# divtiesus_v10_tiesus_del_to.net
KiCad netlist of a schematic drawn in EAGLE
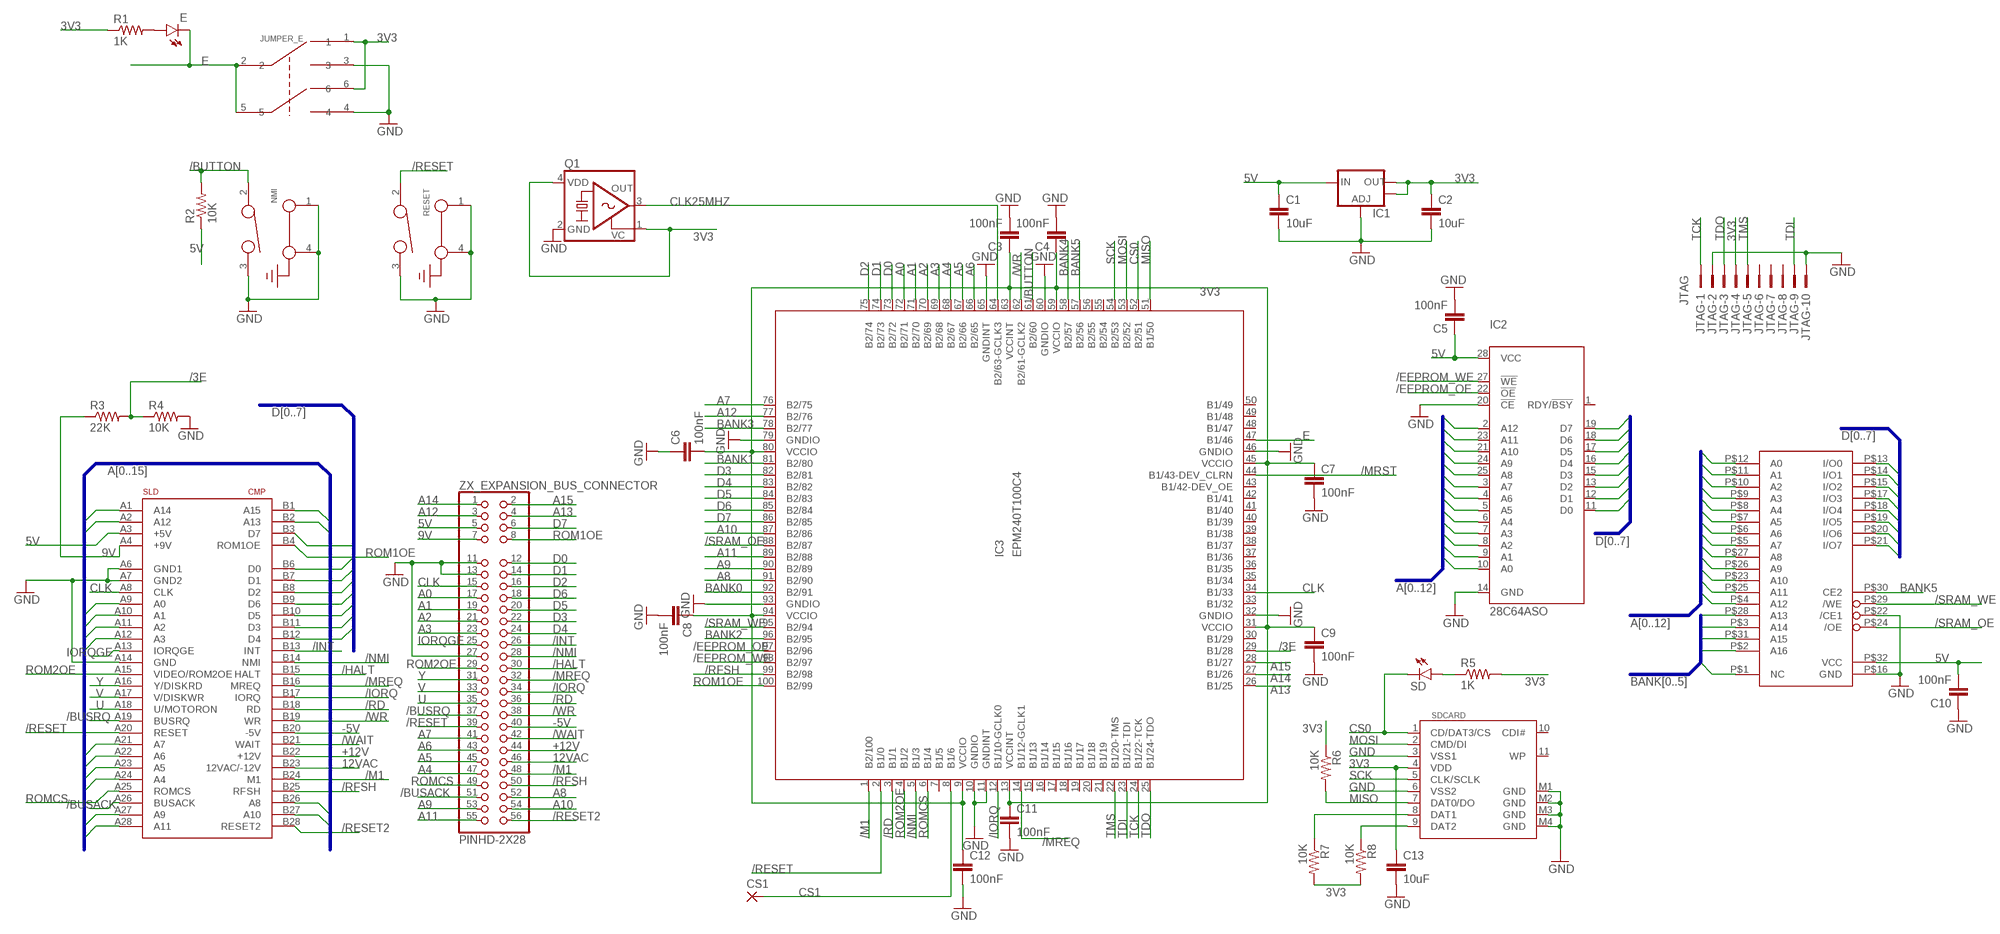
[diagram p0: schematic, sheet 1]

(export (version "E")
  (design (tool "Eeschema 10.0.6"))
  (components
    (comp (ref "C1")
      (value "10uF")
      (footprint "eagle-import:C0805")
      (libsource (lib "eagle-import") (part "C-EUC0805"))
    )
    (comp (ref "C2")
      (value "10uF")
      (footprint "eagle-import:C0805")
      (libsource (lib "eagle-import") (part "C-EUC0805"))
    )
    (comp (ref "C3")
      (value "100nF")
      (footprint "eagle-import:C0603K")
      (libsource (lib "eagle-import") (part "C-EUC0603K"))
    )
    (comp (ref "C4")
      (value "100nF")
      (footprint "eagle-import:C0603K")
      (libsource (lib "eagle-import") (part "C-EUC0603K"))
    )
    (comp (ref "C5")
      (value "100nF")
      (footprint "eagle-import:C0603K")
      (libsource (lib "eagle-import") (part "C-EUC0603K"))
    )
    (comp (ref "C6")
      (value "100nF")
      (footprint "eagle-import:C0603K")
      (libsource (lib "eagle-import") (part "C-EUC0603K"))
    )
    (comp (ref "C7")
      (value "100nF")
      (footprint "eagle-import:C0603K")
      (libsource (lib "eagle-import") (part "C-EUC0603K"))
    )
    (comp (ref "C8")
      (value "100nF")
      (footprint "eagle-import:C0603K")
      (libsource (lib "eagle-import") (part "C-EUC0603K"))
    )
    (comp (ref "C9")
      (value "100nF")
      (footprint "eagle-import:C0603K")
      (libsource (lib "eagle-import") (part "C-EUC0603K"))
    )
    (comp (ref "C10")
      (value "100nF")
      (footprint "eagle-import:C0603K")
      (libsource (lib "eagle-import") (part "C-EUC0603K"))
    )
    (comp (ref "C11")
      (value "100nF")
      (footprint "eagle-import:C0603K")
      (libsource (lib "eagle-import") (part "C-EUC0603K"))
    )
    (comp (ref "C12")
      (value "100nF")
      (footprint "eagle-import:C0603K")
      (libsource (lib "eagle-import") (part "C-EUC0603K"))
    )
    (comp (ref "C13")
      (value "10uF")
      (footprint "eagle-import:C0805")
      (libsource (lib "eagle-import") (part "C-EUC0805"))
    )
    (comp (ref "CS1")
      (value "SMD2")
      (footprint "eagle-import:SMD1,27-2,54")
      (libsource (lib "eagle-import") (part "SMD2"))
    )
    (comp (ref "E")
      (value "LEDCHIPLED_0805")
      (footprint "eagle-import:CHIPLED_0805")
      (libsource (lib "eagle-import") (part "LEDCHIPLED_0805"))
    )
    (comp (ref "IC1")
      (value "V_REG_LM1117SOT223")
      (footprint "eagle-import:SOT223")
      (libsource (lib "eagle-import") (part "V_REG_LM1117SOT223"))
    )
    (comp (ref "IC2")
      (value "28C64ASO")
      (footprint "eagle-import:SO28W")
      (fields (field (name "MPN") "CAT28C64BWI-12"))
      (libsource (lib "eagle-import") (part "2864ASOC"))
    )
    (comp (ref "IC3")
      (value "EPM240T100C4")
      (footprint "eagle-import:TQFP100")
      (libsource (lib "eagle-import") (part "EPM240T100C4"))
    )
    (comp (ref "IC4")
      (value "IS65C1024ALSO32")
      (footprint "eagle-import:SO32-545MIL")
      (libsource (lib "eagle-import") (part "IS65C1024ALSO32"))
    )
    (comp (ref "JTAG")
      (value "JTAG")
      (footprint "eagle-import:PAK100_2500-10")
      (fields (field (name "MF") "3M") (field (name "MPN") "2510-6002UB"))
      (libsource (lib "eagle-import") (part "2510-"))
    )
    (comp (ref "JUMPER_E")
      (value "SWITCH_SMD_6PIN")
      (footprint "eagle-import:SMD-6PIN")
      (libsource (lib "eagle-import") (part "SWITCH_SMD_6PIN"))
    )
    (comp (ref "NMI")
      (value "431256083716")
      (footprint "eagle-import:431256083716")
      (libsource (lib "eagle-import") (part "431256083716"))
    )
    (comp (ref "Q1")
      (value "KXO-VCTCXO-SINE-84")
      (footprint "eagle-import:3.2X2.5_KXO-84-VCTCXO")
      (libsource (lib "eagle-import") (part "KXO-VCTCXO-SINE-84"))
    )
    (comp (ref "R1")
      (value "1K")
      (footprint "eagle-import:R0603")
      (libsource (lib "eagle-import") (part "R-US_R0603"))
    )
    (comp (ref "R2")
      (value "10K")
      (footprint "eagle-import:R0603")
      (libsource (lib "eagle-import") (part "R-US_R0603"))
    )
    (comp (ref "R3")
      (value "22K")
      (footprint "eagle-import:R0603")
      (libsource (lib "eagle-import") (part "R-US_R0603"))
    )
    (comp (ref "R4")
      (value "10K")
      (footprint "eagle-import:R0603")
      (libsource (lib "eagle-import") (part "R-US_R0603"))
    )
    (comp (ref "R5")
      (value "1K")
      (footprint "eagle-import:R0603")
      (libsource (lib "eagle-import") (part "R-US_R0603"))
    )
    (comp (ref "R6")
      (value "10K")
      (footprint "eagle-import:R0603")
      (libsource (lib "eagle-import") (part "R-US_R0603"))
    )
    (comp (ref "R7")
      (value "10K")
      (footprint "eagle-import:R0603")
      (libsource (lib "eagle-import") (part "R-US_R0603"))
    )
    (comp (ref "R8")
      (value "10K")
      (footprint "eagle-import:R0603")
      (libsource (lib "eagle-import") (part "R-US_R0603"))
    )
    (comp (ref "RESET")
      (value "431256083716")
      (footprint "eagle-import:431256083716")
      (libsource (lib "eagle-import") (part "431256083716"))
    )
    (comp (ref "SD")
      (value "LEDCHIPLED_0805")
      (footprint "eagle-import:CHIPLED_0805")
      (libsource (lib "eagle-import") (part "LEDCHIPLED_0805"))
    )
    (comp (ref "SDCARD")
      (value "SDCARD")
      (footprint "eagle-import:SDCMF-10915W010")
      (libsource (lib "eagle-import") (part "SDCARD"))
    )
    (comp (ref "U$1")
      (value "CONECTOR_BUS_TRASERO")
      (footprint "eagle-import:CONECTOR_SIMPLE_CARA")
      (libsource (lib "eagle-import") (part "CONECTOR_BUS_TRASERO"))
    )
    (comp (ref "ZX_EXPANSION_BUS_CONNECTOR")
      (value "PINHD-2X28")
      (footprint "eagle-import:2X28")
      (libsource (lib "eagle-import") (part "PINHD-2X28"))
    )
  )
  (nets
    (net (code "1") (name "/+12V") (class "Default")
      (node (ref "U$1") (pin "B22") (pinfunction "+12V_B22") (pintype "bidirectional"))
      (node (ref "ZX_EXPANSION_BUS_CONNECTOR") (pin "44") (pinfunction "44_44") (pintype "passive"))
    )
    (net (code "2") (name "/-5V") (class "Default")
      (node (ref "U$1") (pin "B20") (pinfunction "-5V_B20") (pintype "bidirectional"))
      (node (ref "ZX_EXPANSION_BUS_CONNECTOR") (pin "40") (pinfunction "40_40") (pintype "passive"))
    )
    (net (code "3") (name "/3V3") (class "Default")
      (node (ref "C11") (pin "1") (pinfunction "1_1") (pintype "passive"))
      (node (ref "C12") (pin "1") (pinfunction "1_1") (pintype "passive"))
      (node (ref "C13") (pin "1") (pinfunction "1_1") (pintype "passive"))
      (node (ref "C2") (pin "1") (pinfunction "1_1") (pintype "passive"))
      (node (ref "C3") (pin "1") (pinfunction "1_1") (pintype "passive"))
      (node (ref "C4") (pin "1") (pinfunction "1_1") (pintype "passive"))
      (node (ref "C6") (pin "2") (pinfunction "2_2") (pintype "passive"))
      (node (ref "C7") (pin "1") (pinfunction "1_1") (pintype "passive"))
      (node (ref "C8") (pin "1") (pinfunction "1_1") (pintype "passive"))
      (node (ref "C9") (pin "1") (pinfunction "1_1") (pintype "passive"))
      (node (ref "IC1") (pin "2") (pinfunction "OUT_2") (pintype "output"))
      (node (ref "IC1") (pin "4") (pinfunction "OUT_4") (pintype "output"))
      (node (ref "IC3") (pin "13") (pinfunction "VCCINT_13") (pintype "power_in"))
      (node (ref "IC3") (pin "31") (pinfunction "VCCIO_31") (pintype "power_in"))
      (node (ref "IC3") (pin "45") (pinfunction "VCCIO_45") (pintype "power_in"))
      (node (ref "IC3") (pin "59") (pinfunction "VCCIO_59") (pintype "power_in"))
      (node (ref "IC3") (pin "63") (pinfunction "VCCINT_63") (pintype "power_in"))
      (node (ref "IC3") (pin "80") (pinfunction "VCCIO_80") (pintype "power_in"))
      (node (ref "IC3") (pin "9") (pinfunction "VCCIO_9") (pintype "power_in"))
      (node (ref "IC3") (pin "94") (pinfunction "VCCIO_94") (pintype "power_in"))
      (node (ref "JTAG") (pin "4") (pinfunction "KL_4") (pintype "passive"))
      (node (ref "JUMPER_E") (pin "1") (pinfunction "1_1") (pintype "bidirectional"))
      (node (ref "JUMPER_E") (pin "6") (pinfunction "6_6") (pintype "bidirectional"))
      (node (ref "Q1") (pin "1") (pinfunction "VC_1") (pintype "input"))
      (node (ref "Q1") (pin "4") (pinfunction "VDD_4") (pintype "power_in"))
      (node (ref "R1") (pin "1") (pinfunction "1_1") (pintype "passive"))
      (node (ref "R5") (pin "2") (pinfunction "2_2") (pintype "passive"))
      (node (ref "R6") (pin "1") (pinfunction "1_1") (pintype "passive"))
      (node (ref "R7") (pin "2") (pinfunction "2_2") (pintype "passive"))
      (node (ref "R8") (pin "2") (pinfunction "2_2") (pintype "passive"))
      (node (ref "SDCARD") (pin "4") (pinfunction "VDD_4") (pintype "power_in"))
    )
    (net (code "4") (name "/5V") (class "Default")
      (node (ref "C1") (pin "1") (pinfunction "1_1") (pintype "passive"))
      (node (ref "C10") (pin "2") (pinfunction "2_2") (pintype "passive"))
      (node (ref "C5") (pin "1") (pinfunction "1_1") (pintype "passive"))
      (node (ref "IC1") (pin "3") (pinfunction "IN_3") (pintype "input"))
      (node (ref "IC2") (pin "28") (pinfunction "VCC_28") (pintype "power_in"))
      (node (ref "IC4") (pin "P$32") (pinfunction "VCC_P$32") (pintype "input"))
      (node (ref "R2") (pin "1") (pinfunction "1_1") (pintype "passive"))
      (node (ref "U$1") (pin "A3") (pinfunction "+5V_A3") (pintype "bidirectional"))
      (node (ref "ZX_EXPANSION_BUS_CONNECTOR") (pin "5") (pinfunction "5_5") (pintype "passive"))
    )
    (net (code "5") (name "/9V") (class "Default")
      (node (ref "R3") (pin "1") (pinfunction "1_1") (pintype "passive"))
      (node (ref "U$1") (pin "A4") (pinfunction "+9V_A4") (pintype "bidirectional"))
      (node (ref "ZX_EXPANSION_BUS_CONNECTOR") (pin "7") (pinfunction "7_7") (pintype "passive"))
    )
    (net (code "6") (name "/12VAC") (class "Default")
      (node (ref "U$1") (pin "B23") (pinfunction "12VAC/-12V_B23") (pintype "bidirectional"))
      (node (ref "ZX_EXPANSION_BUS_CONNECTOR") (pin "46") (pinfunction "46_46") (pintype "passive"))
    )
    (net (code "7") (name "/A0") (class "Default")
      (node (ref "IC2") (pin "10") (pinfunction "A0_10") (pintype "input"))
      (node (ref "IC3") (pin "72") (pinfunction "B2/71_72") (pintype "bidirectional"))
      (node (ref "IC4") (pin "P$12") (pinfunction "A0_P$12") (pintype "input"))
      (node (ref "U$1") (pin "A9") (pinfunction "A0_A9") (pintype "bidirectional"))
      (node (ref "ZX_EXPANSION_BUS_CONNECTOR") (pin "17") (pinfunction "17_17") (pintype "passive"))
    )
    (net (code "8") (name "/A1") (class "Default")
      (node (ref "IC2") (pin "9") (pinfunction "A1_9") (pintype "input"))
      (node (ref "IC3") (pin "71") (pinfunction "B2/70_71") (pintype "bidirectional"))
      (node (ref "IC4") (pin "P$11") (pinfunction "A1_P$11") (pintype "input"))
      (node (ref "U$1") (pin "A10") (pinfunction "A1_A10") (pintype "bidirectional"))
      (node (ref "ZX_EXPANSION_BUS_CONNECTOR") (pin "19") (pinfunction "19_19") (pintype "passive"))
    )
    (net (code "9") (name "/A2") (class "Default")
      (node (ref "IC2") (pin "8") (pinfunction "A2_8") (pintype "input"))
      (node (ref "IC3") (pin "70") (pinfunction "B2/69_70") (pintype "bidirectional"))
      (node (ref "IC4") (pin "P$10") (pinfunction "A2_P$10") (pintype "input"))
      (node (ref "U$1") (pin "A11") (pinfunction "A2_A11") (pintype "bidirectional"))
      (node (ref "ZX_EXPANSION_BUS_CONNECTOR") (pin "21") (pinfunction "21_21") (pintype "passive"))
    )
    (net (code "10") (name "/A3") (class "Default")
      (node (ref "IC2") (pin "7") (pinfunction "A3_7") (pintype "input"))
      (node (ref "IC3") (pin "69") (pinfunction "B2/68_69") (pintype "bidirectional"))
      (node (ref "IC4") (pin "P$9") (pinfunction "A3_P$9") (pintype "input"))
      (node (ref "U$1") (pin "A12") (pinfunction "A3_A12") (pintype "bidirectional"))
      (node (ref "ZX_EXPANSION_BUS_CONNECTOR") (pin "23") (pinfunction "23_23") (pintype "passive"))
    )
    (net (code "11") (name "/A4") (class "Default")
      (node (ref "IC2") (pin "6") (pinfunction "A4_6") (pintype "input"))
      (node (ref "IC3") (pin "68") (pinfunction "B2/67_68") (pintype "bidirectional"))
      (node (ref "IC4") (pin "P$8") (pinfunction "A4_P$8") (pintype "input"))
      (node (ref "U$1") (pin "A24") (pinfunction "A4_A24") (pintype "bidirectional"))
      (node (ref "ZX_EXPANSION_BUS_CONNECTOR") (pin "47") (pinfunction "47_47") (pintype "passive"))
    )
    (net (code "12") (name "/A5") (class "Default")
      (node (ref "IC2") (pin "5") (pinfunction "A5_5") (pintype "input"))
      (node (ref "IC3") (pin "67") (pinfunction "B2/66_67") (pintype "bidirectional"))
      (node (ref "IC4") (pin "P$7") (pinfunction "A5_P$7") (pintype "input"))
      (node (ref "U$1") (pin "A23") (pinfunction "A5_A23") (pintype "bidirectional"))
      (node (ref "ZX_EXPANSION_BUS_CONNECTOR") (pin "45") (pinfunction "45_45") (pintype "passive"))
    )
    (net (code "13") (name "/A6") (class "Default")
      (node (ref "IC2") (pin "4") (pinfunction "A6_4") (pintype "input"))
      (node (ref "IC3") (pin "66") (pinfunction "B2/65_66") (pintype "bidirectional"))
      (node (ref "IC4") (pin "P$6") (pinfunction "A6_P$6") (pintype "input"))
      (node (ref "U$1") (pin "A22") (pinfunction "A6_A22") (pintype "bidirectional"))
      (node (ref "ZX_EXPANSION_BUS_CONNECTOR") (pin "43") (pinfunction "43_43") (pintype "passive"))
    )
    (net (code "14") (name "/A7") (class "Default")
      (node (ref "IC2") (pin "3") (pinfunction "A7_3") (pintype "input"))
      (node (ref "IC3") (pin "76") (pinfunction "B2/75_76") (pintype "bidirectional"))
      (node (ref "IC4") (pin "P$5") (pinfunction "A7_P$5") (pintype "input"))
      (node (ref "U$1") (pin "A21") (pinfunction "A7_A21") (pintype "bidirectional"))
      (node (ref "ZX_EXPANSION_BUS_CONNECTOR") (pin "41") (pinfunction "41_41") (pintype "passive"))
    )
    (net (code "15") (name "/A8") (class "Default")
      (node (ref "IC2") (pin "25") (pinfunction "A8_25") (pintype "input"))
      (node (ref "IC3") (pin "91") (pinfunction "B2/90_91") (pintype "bidirectional"))
      (node (ref "IC4") (pin "P$27") (pinfunction "A8_P$27") (pintype "input"))
      (node (ref "U$1") (pin "B26") (pinfunction "A8_B26") (pintype "bidirectional"))
      (node (ref "ZX_EXPANSION_BUS_CONNECTOR") (pin "52") (pinfunction "52_52") (pintype "passive"))
    )
    (net (code "16") (name "/A9") (class "Default")
      (node (ref "IC2") (pin "24") (pinfunction "A9_24") (pintype "input"))
      (node (ref "IC3") (pin "90") (pinfunction "B2/89_90") (pintype "bidirectional"))
      (node (ref "IC4") (pin "P$26") (pinfunction "A9_P$26") (pintype "input"))
      (node (ref "U$1") (pin "A27") (pinfunction "A9_A27") (pintype "bidirectional"))
      (node (ref "ZX_EXPANSION_BUS_CONNECTOR") (pin "53") (pinfunction "53_53") (pintype "passive"))
    )
    (net (code "17") (name "/A10") (class "Default")
      (node (ref "IC2") (pin "21") (pinfunction "A10_21") (pintype "input"))
      (node (ref "IC3") (pin "87") (pinfunction "B2/86_87") (pintype "bidirectional"))
      (node (ref "IC4") (pin "P$23") (pinfunction "A10_P$23") (pintype "input"))
      (node (ref "U$1") (pin "B27") (pinfunction "A10_B27") (pintype "bidirectional"))
      (node (ref "ZX_EXPANSION_BUS_CONNECTOR") (pin "54") (pinfunction "54_54") (pintype "passive"))
    )
    (net (code "18") (name "/A11") (class "Default")
      (node (ref "IC2") (pin "23") (pinfunction "A11_23") (pintype "input"))
      (node (ref "IC3") (pin "89") (pinfunction "B2/88_89") (pintype "bidirectional"))
      (node (ref "IC4") (pin "P$25") (pinfunction "A11_P$25") (pintype "input"))
      (node (ref "U$1") (pin "A28") (pinfunction "A11_A28") (pintype "bidirectional"))
      (node (ref "ZX_EXPANSION_BUS_CONNECTOR") (pin "55") (pinfunction "55_55") (pintype "passive"))
    )
    (net (code "19") (name "/A12") (class "Default")
      (node (ref "IC2") (pin "2") (pinfunction "A12_2") (pintype "input"))
      (node (ref "IC3") (pin "77") (pinfunction "B2/76_77") (pintype "bidirectional"))
      (node (ref "IC4") (pin "P$4") (pinfunction "A12_P$4") (pintype "input"))
      (node (ref "U$1") (pin "A2") (pinfunction "A12_A2") (pintype "bidirectional"))
      (node (ref "ZX_EXPANSION_BUS_CONNECTOR") (pin "3") (pinfunction "3_3") (pintype "passive"))
    )
    (net (code "20") (name "/A13") (class "Default")
      (node (ref "IC3") (pin "26") (pinfunction "B1/25_26") (pintype "bidirectional"))
      (node (ref "U$1") (pin "B2") (pinfunction "A13_B2") (pintype "bidirectional"))
      (node (ref "ZX_EXPANSION_BUS_CONNECTOR") (pin "4") (pinfunction "4_4") (pintype "passive"))
    )
    (net (code "21") (name "/A14") (class "Default")
      (node (ref "IC3") (pin "27") (pinfunction "B1/26_27") (pintype "bidirectional"))
      (node (ref "U$1") (pin "A1") (pinfunction "A14_A1") (pintype "bidirectional"))
      (node (ref "ZX_EXPANSION_BUS_CONNECTOR") (pin "1") (pinfunction "1_1") (pintype "passive"))
    )
    (net (code "22") (name "/A15") (class "Default")
      (node (ref "IC3") (pin "28") (pinfunction "B1/27_28") (pintype "bidirectional"))
      (node (ref "U$1") (pin "B1") (pinfunction "A15_B1") (pintype "bidirectional"))
      (node (ref "ZX_EXPANSION_BUS_CONNECTOR") (pin "2") (pinfunction "2_2") (pintype "passive"))
    )
    (net (code "25") (name "/BANK0") (class "Default")
      (node (ref "IC3") (pin "92") (pinfunction "B2/91_92") (pintype "bidirectional"))
      (node (ref "IC4") (pin "P$28") (pinfunction "A13_P$28") (pintype "input"))
    )
    (net (code "26") (name "/BANK1") (class "Default")
      (node (ref "IC3") (pin "81") (pinfunction "B2/80_81") (pintype "bidirectional"))
      (node (ref "IC4") (pin "P$3") (pinfunction "A14_P$3") (pintype "input"))
    )
    (net (code "27") (name "/BANK2") (class "Default")
      (node (ref "IC3") (pin "96") (pinfunction "B2/95_96") (pintype "bidirectional"))
      (node (ref "IC4") (pin "P$31") (pinfunction "A15_P$31") (pintype "input"))
    )
    (net (code "28") (name "/BANK3") (class "Default")
      (node (ref "IC3") (pin "78") (pinfunction "B2/77_78") (pintype "bidirectional"))
      (node (ref "IC4") (pin "P$2") (pinfunction "A16_P$2") (pintype "input"))
    )
    (net (code "29") (name "/BANK4") (class "Default")
      (node (ref "IC3") (pin "58") (pinfunction "B2/57_58") (pintype "bidirectional"))
      (node (ref "IC4") (pin "P$1") (pinfunction "NC_P$1") (pintype "input"))
    )
    (net (code "30") (name "/BANK5") (class "Default")
      (node (ref "IC3") (pin "57") (pinfunction "B2/56_57") (pintype "bidirectional"))
      (node (ref "IC4") (pin "P$30") (pinfunction "CE2_P$30") (pintype "input"))
    )
    (net (code "32") (name "/CLK") (class "Default")
      (node (ref "IC3") (pin "34") (pinfunction "B1/33_34") (pintype "bidirectional"))
      (node (ref "U$1") (pin "A8") (pinfunction "CLK_A8") (pintype "bidirectional"))
      (node (ref "ZX_EXPANSION_BUS_CONNECTOR") (pin "15") (pinfunction "15_15") (pintype "passive"))
    )
    (net (code "33") (name "/CLK25MHZ") (class "Default")
      (node (ref "IC3") (pin "64") (pinfunction "B2/63-GCLK3_64") (pintype "bidirectional"))
      (node (ref "Q1") (pin "3") (pinfunction "OUT_3") (pintype "output"))
    )
    (net (code "34") (name "/CS0") (class "Default")
      (node (ref "IC3") (pin "52") (pinfunction "B2/51_52") (pintype "bidirectional"))
      (node (ref "SD") (pin "C") (pinfunction "C_C") (pintype "passive"))
      (node (ref "SDCARD") (pin "1") (pinfunction "CD/DAT3/CS_1") (pintype "bidirectional"))
    )
    (net (code "35") (name "/CS1") (class "Default")
      (node (ref "CS1") (pin "1") (pinfunction "P_1") (pintype "passive"))
      (node (ref "IC3") (pin "8") (pinfunction "B1/6_8") (pintype "bidirectional"))
    )
    (net (code "36") (name "/D0") (class "Default")
      (node (ref "IC2") (pin "11") (pinfunction "D0_11") (pintype "tri_state"))
      (node (ref "IC3") (pin "73") (pinfunction "B2/72_73") (pintype "bidirectional"))
      (node (ref "IC4") (pin "P$13") (pinfunction "I/O0_P$13") (pintype "bidirectional"))
      (node (ref "U$1") (pin "B6") (pinfunction "D0_B6") (pintype "bidirectional"))
      (node (ref "ZX_EXPANSION_BUS_CONNECTOR") (pin "12") (pinfunction "12_12") (pintype "passive"))
    )
    (net (code "37") (name "/D1") (class "Default")
      (node (ref "IC2") (pin "12") (pinfunction "D1_12") (pintype "tri_state"))
      (node (ref "IC3") (pin "74") (pinfunction "B2/73_74") (pintype "bidirectional"))
      (node (ref "IC4") (pin "P$14") (pinfunction "I/O1_P$14") (pintype "bidirectional"))
      (node (ref "U$1") (pin "B7") (pinfunction "D1_B7") (pintype "bidirectional"))
      (node (ref "ZX_EXPANSION_BUS_CONNECTOR") (pin "14") (pinfunction "14_14") (pintype "passive"))
    )
    (net (code "38") (name "/D2") (class "Default")
      (node (ref "IC2") (pin "13") (pinfunction "D2_13") (pintype "tri_state"))
      (node (ref "IC3") (pin "75") (pinfunction "B2/74_75") (pintype "bidirectional"))
      (node (ref "IC4") (pin "P$15") (pinfunction "I/O2_P$15") (pintype "bidirectional"))
      (node (ref "U$1") (pin "B8") (pinfunction "D2_B8") (pintype "bidirectional"))
      (node (ref "ZX_EXPANSION_BUS_CONNECTOR") (pin "16") (pinfunction "16_16") (pintype "passive"))
    )
    (net (code "39") (name "/D3") (class "Default")
      (node (ref "IC2") (pin "15") (pinfunction "D3_15") (pintype "tri_state"))
      (node (ref "IC3") (pin "82") (pinfunction "B2/81_82") (pintype "bidirectional"))
      (node (ref "IC4") (pin "P$17") (pinfunction "I/O3_P$17") (pintype "bidirectional"))
      (node (ref "U$1") (pin "B11") (pinfunction "D3_B11") (pintype "bidirectional"))
      (node (ref "ZX_EXPANSION_BUS_CONNECTOR") (pin "22") (pinfunction "22_22") (pintype "passive"))
    )
    (net (code "40") (name "/D4") (class "Default")
      (node (ref "IC2") (pin "16") (pinfunction "D4_16") (pintype "tri_state"))
      (node (ref "IC3") (pin "83") (pinfunction "B2/82_83") (pintype "bidirectional"))
      (node (ref "IC4") (pin "P$18") (pinfunction "I/O4_P$18") (pintype "bidirectional"))
      (node (ref "U$1") (pin "B12") (pinfunction "D4_B12") (pintype "bidirectional"))
      (node (ref "ZX_EXPANSION_BUS_CONNECTOR") (pin "24") (pinfunction "24_24") (pintype "passive"))
    )
    (net (code "41") (name "/D5") (class "Default")
      (node (ref "IC2") (pin "17") (pinfunction "D5_17") (pintype "tri_state"))
      (node (ref "IC3") (pin "84") (pinfunction "B2/83_84") (pintype "bidirectional"))
      (node (ref "IC4") (pin "P$19") (pinfunction "I/O5_P$19") (pintype "bidirectional"))
      (node (ref "U$1") (pin "B10") (pinfunction "D5_B10") (pintype "bidirectional"))
      (node (ref "ZX_EXPANSION_BUS_CONNECTOR") (pin "20") (pinfunction "20_20") (pintype "passive"))
    )
    (net (code "42") (name "/D6") (class "Default")
      (node (ref "IC2") (pin "18") (pinfunction "D6_18") (pintype "tri_state"))
      (node (ref "IC3") (pin "85") (pinfunction "B2/84_85") (pintype "bidirectional"))
      (node (ref "IC4") (pin "P$20") (pinfunction "I/O6_P$20") (pintype "bidirectional"))
      (node (ref "U$1") (pin "B9") (pinfunction "D6_B9") (pintype "bidirectional"))
      (node (ref "ZX_EXPANSION_BUS_CONNECTOR") (pin "18") (pinfunction "18_18") (pintype "passive"))
    )
    (net (code "43") (name "/D7") (class "Default")
      (node (ref "IC2") (pin "19") (pinfunction "D7_19") (pintype "tri_state"))
      (node (ref "IC3") (pin "86") (pinfunction "B2/85_86") (pintype "bidirectional"))
      (node (ref "IC4") (pin "P$21") (pinfunction "I/O7_P$21") (pintype "bidirectional"))
      (node (ref "U$1") (pin "B3") (pinfunction "D7_B3") (pintype "bidirectional"))
      (node (ref "ZX_EXPANSION_BUS_CONNECTOR") (pin "6") (pinfunction "6_6") (pintype "passive"))
    )
    (net (code "45") (name "/E") (class "Default")
      (node (ref "E") (pin "C") (pinfunction "C_C") (pintype "passive"))
      (node (ref "IC3") (pin "47") (pinfunction "B1/46_47") (pintype "bidirectional"))
      (node (ref "JUMPER_E") (pin "2") (pinfunction "2_2") (pintype "bidirectional"))
      (node (ref "JUMPER_E") (pin "5") (pinfunction "5_5") (pintype "bidirectional"))
    )
    (net (code "46") (name "/IORQGE") (class "Default")
      (node (ref "U$1") (pin "A13") (pinfunction "IORQGE_A13") (pintype "bidirectional"))
      (node (ref "ZX_EXPANSION_BUS_CONNECTOR") (pin "25") (pinfunction "25_25") (pintype "passive"))
    )
    (net (code "47") (name "/MISO") (class "Default")
      (node (ref "IC3") (pin "51") (pinfunction "B1/50_51") (pintype "bidirectional"))
      (node (ref "R6") (pin "2") (pinfunction "2_2") (pintype "passive"))
      (node (ref "SDCARD") (pin "7") (pinfunction "DAT0/DO_7") (pintype "bidirectional"))
    )
    (net (code "48") (name "/MOSI") (class "Default")
      (node (ref "IC3") (pin "53") (pinfunction "B2/52_53") (pintype "bidirectional"))
      (node (ref "SDCARD") (pin "2") (pinfunction "CMD/DI_2") (pintype "bidirectional"))
    )
    (net (code "49") (name "/ROM1OE") (class "Default")
      (node (ref "IC3") (pin "100") (pinfunction "B2/99_100") (pintype "bidirectional"))
      (node (ref "U$1") (pin "B4") (pinfunction "ROM1OE_B4") (pintype "bidirectional"))
      (node (ref "ZX_EXPANSION_BUS_CONNECTOR") (pin "8") (pinfunction "8_8") (pintype "passive"))
    )
    (net (code "50") (name "/ROM2OE") (class "Default")
      (node (ref "IC3") (pin "4") (pinfunction "B1/2_4") (pintype "bidirectional"))
      (node (ref "U$1") (pin "A15") (pinfunction "VIDEO/ROM2OE_A15") (pintype "bidirectional"))
      (node (ref "ZX_EXPANSION_BUS_CONNECTOR") (pin "29") (pinfunction "29_29") (pintype "passive"))
    )
    (net (code "51") (name "/ROMCS") (class "Default")
      (node (ref "IC3") (pin "6") (pinfunction "B1/4_6") (pintype "bidirectional"))
      (node (ref "U$1") (pin "A25") (pinfunction "ROMCS_A25") (pintype "bidirectional"))
      (node (ref "ZX_EXPANSION_BUS_CONNECTOR") (pin "49") (pinfunction "49_49") (pintype "passive"))
    )
    (net (code "52") (name "/SCK") (class "Default")
      (node (ref "IC3") (pin "54") (pinfunction "B2/53_54") (pintype "bidirectional"))
      (node (ref "SDCARD") (pin "5") (pinfunction "CLK/SCLK_5") (pintype "bidirectional"))
    )
    (net (code "53") (name "/TCK") (class "Default")
      (node (ref "IC3") (pin "24") (pinfunction "B1/22-TCK_24") (pintype "input"))
      (node (ref "JTAG") (pin "1") (pinfunction "KL_1") (pintype "passive"))
    )
    (net (code "54") (name "/TDI") (class "Default")
      (node (ref "IC3") (pin "23") (pinfunction "B1/21-TDI_23") (pintype "input"))
      (node (ref "JTAG") (pin "9") (pinfunction "KL_9") (pintype "passive"))
    )
    (net (code "55") (name "/TDO") (class "Default")
      (node (ref "IC3") (pin "25") (pinfunction "B1/24-TDO_25") (pintype "output"))
      (node (ref "JTAG") (pin "3") (pinfunction "KL_3") (pintype "passive"))
    )
    (net (code "56") (name "/TMS") (class "Default")
      (node (ref "IC3") (pin "22") (pinfunction "B1/20-TMS_22") (pintype "input"))
      (node (ref "JTAG") (pin "5") (pinfunction "KL_5") (pintype "passive"))
    )
    (net (code "57") (name "/U") (class "Default")
      (node (ref "U$1") (pin "A18") (pinfunction "U/MOTORON_A18") (pintype "bidirectional"))
      (node (ref "ZX_EXPANSION_BUS_CONNECTOR") (pin "35") (pinfunction "35_35") (pintype "passive"))
    )
    (net (code "58") (name "/V") (class "Default")
      (node (ref "U$1") (pin "A17") (pinfunction "V/DISKWR_A17") (pintype "bidirectional"))
      (node (ref "ZX_EXPANSION_BUS_CONNECTOR") (pin "33") (pinfunction "33_33") (pintype "passive"))
    )
    (net (code "59") (name "/Y") (class "Default")
      (node (ref "U$1") (pin "A16") (pinfunction "Y/DISKRD_A16") (pintype "bidirectional"))
      (node (ref "ZX_EXPANSION_BUS_CONNECTOR") (pin "31") (pinfunction "31_31") (pintype "passive"))
    )
    (net (code "60") (name "/{slash}3E") (class "Default")
      (node (ref "IC3") (pin "29") (pinfunction "B1/28_29") (pintype "bidirectional"))
      (node (ref "R3") (pin "2") (pinfunction "2_2") (pintype "passive"))
      (node (ref "R4") (pin "1") (pinfunction "1_1") (pintype "passive"))
    )
    (net (code "61") (name "/{slash}BUSACK") (class "Default")
      (node (ref "U$1") (pin "A26") (pinfunction "BUSACK_A26") (pintype "bidirectional"))
      (node (ref "ZX_EXPANSION_BUS_CONNECTOR") (pin "51") (pinfunction "51_51") (pintype "passive"))
    )
    (net (code "62") (name "/{slash}BUSRQ") (class "Default")
      (node (ref "U$1") (pin "A19") (pinfunction "BUSRQ_A19") (pintype "bidirectional"))
      (node (ref "ZX_EXPANSION_BUS_CONNECTOR") (pin "37") (pinfunction "37_37") (pintype "passive"))
    )
    (net (code "63") (name "/{slash}BUTTON") (class "Default")
      (node (ref "IC3") (pin "61") (pinfunction "B2/60_61") (pintype "bidirectional"))
      (node (ref "NMI") (pin "2") (pinfunction "2_2") (pintype "passive"))
      (node (ref "R2") (pin "2") (pinfunction "2_2") (pintype "passive"))
    )
    (net (code "64") (name "/{slash}EEPROM_OE") (class "Default")
      (node (ref "IC2") (pin "22") (pinfunction "~{OE}_22") (pintype "input"))
      (node (ref "IC3") (pin "97") (pinfunction "B2/96_97") (pintype "bidirectional"))
    )
    (net (code "65") (name "/{slash}EEPROM_WE") (class "Default")
      (node (ref "IC2") (pin "27") (pinfunction "~{WE}_27") (pintype "input"))
      (node (ref "IC3") (pin "98") (pinfunction "B2/97_98") (pintype "bidirectional"))
    )
    (net (code "66") (name "/{slash}HALT") (class "Default")
      (node (ref "U$1") (pin "B15") (pinfunction "HALT_B15") (pintype "bidirectional"))
      (node (ref "ZX_EXPANSION_BUS_CONNECTOR") (pin "30") (pinfunction "30_30") (pintype "passive"))
    )
    (net (code "67") (name "/{slash}INT") (class "Default")
      (node (ref "U$1") (pin "B13") (pinfunction "INT_B13") (pintype "bidirectional"))
      (node (ref "ZX_EXPANSION_BUS_CONNECTOR") (pin "26") (pinfunction "26_26") (pintype "passive"))
    )
    (net (code "68") (name "/{slash}IORQ") (class "Default")
      (node (ref "IC3") (pin "12") (pinfunction "B1/10-GCLK0_12") (pintype "bidirectional"))
      (node (ref "U$1") (pin "B17") (pinfunction "IORQ_B17") (pintype "bidirectional"))
      (node (ref "ZX_EXPANSION_BUS_CONNECTOR") (pin "34") (pinfunction "34_34") (pintype "passive"))
    )
    (net (code "69") (name "/{slash}M1") (class "Default")
      (node (ref "IC3") (pin "1") (pinfunction "B2/100_1") (pintype "bidirectional"))
      (node (ref "U$1") (pin "B24") (pinfunction "M1_B24") (pintype "bidirectional"))
      (node (ref "ZX_EXPANSION_BUS_CONNECTOR") (pin "48") (pinfunction "48_48") (pintype "passive"))
    )
    (net (code "70") (name "/{slash}MREQ") (class "Default")
      (node (ref "IC3") (pin "14") (pinfunction "B1/12-GCLK1_14") (pintype "bidirectional"))
      (node (ref "U$1") (pin "B16") (pinfunction "MREQ_B16") (pintype "bidirectional"))
      (node (ref "ZX_EXPANSION_BUS_CONNECTOR") (pin "32") (pinfunction "32_32") (pintype "passive"))
    )
    (net (code "71") (name "/{slash}MRST") (class "Default")
      (node (ref "IC3") (pin "44") (pinfunction "B1/43-DEV_CLRN_44") (pintype "bidirectional"))
    )
    (net (code "72") (name "/{slash}NMI") (class "Default")
      (node (ref "IC3") (pin "5") (pinfunction "B1/3_5") (pintype "bidirectional"))
      (node (ref "U$1") (pin "B14") (pinfunction "NMI_B14") (pintype "bidirectional"))
      (node (ref "ZX_EXPANSION_BUS_CONNECTOR") (pin "28") (pinfunction "28_28") (pintype "passive"))
    )
    (net (code "73") (name "/{slash}RD") (class "Default")
      (node (ref "IC3") (pin "3") (pinfunction "B1/1_3") (pintype "bidirectional"))
      (node (ref "U$1") (pin "B18") (pinfunction "RD_B18") (pintype "bidirectional"))
      (node (ref "ZX_EXPANSION_BUS_CONNECTOR") (pin "36") (pinfunction "36_36") (pintype "passive"))
    )
    (net (code "74") (name "/{slash}RESET") (class "Default")
      (node (ref "IC3") (pin "2") (pinfunction "B1/0_2") (pintype "bidirectional"))
      (node (ref "RESET") (pin "2") (pinfunction "2_2") (pintype "passive"))
      (node (ref "U$1") (pin "A20") (pinfunction "RESET_A20") (pintype "bidirectional"))
      (node (ref "ZX_EXPANSION_BUS_CONNECTOR") (pin "39") (pinfunction "39_39") (pintype "passive"))
    )
    (net (code "75") (name "/{slash}RESET2") (class "Default")
      (node (ref "U$1") (pin "B28") (pinfunction "RESET2_B28") (pintype "bidirectional"))
      (node (ref "ZX_EXPANSION_BUS_CONNECTOR") (pin "56") (pinfunction "56_56") (pintype "passive"))
    )
    (net (code "76") (name "/{slash}RFSH") (class "Default")
      (node (ref "IC3") (pin "99") (pinfunction "B2/98_99") (pintype "bidirectional"))
      (node (ref "U$1") (pin "B25") (pinfunction "RFSH_B25") (pintype "bidirectional"))
      (node (ref "ZX_EXPANSION_BUS_CONNECTOR") (pin "50") (pinfunction "50_50") (pintype "passive"))
    )
    (net (code "77") (name "/{slash}SRAM_OE") (class "Default")
      (node (ref "IC3") (pin "88") (pinfunction "B2/87_88") (pintype "bidirectional"))
      (node (ref "IC4") (pin "P$24") (pinfunction "/OE_P$24") (pintype "input"))
    )
    (net (code "78") (name "/{slash}SRAM_WE") (class "Default")
      (node (ref "IC3") (pin "95") (pinfunction "B2/94_95") (pintype "bidirectional"))
      (node (ref "IC4") (pin "P$29") (pinfunction "/WE_P$29") (pintype "input"))
    )
    (net (code "79") (name "/{slash}WAIT") (class "Default")
      (node (ref "U$1") (pin "B21") (pinfunction "WAIT_B21") (pintype "bidirectional"))
      (node (ref "ZX_EXPANSION_BUS_CONNECTOR") (pin "42") (pinfunction "42_42") (pintype "passive"))
    )
    (net (code "80") (name "/{slash}WR") (class "Default")
      (node (ref "IC3") (pin "62") (pinfunction "B2/61-GCLK2_62") (pintype "bidirectional"))
      (node (ref "U$1") (pin "B19") (pinfunction "WR_B19") (pintype "bidirectional"))
      (node (ref "ZX_EXPANSION_BUS_CONNECTOR") (pin "38") (pinfunction "38_38") (pintype "passive"))
    )
    (net (code "81") (name "GND") (class "Default")
      (node (ref "C1") (pin "2") (pinfunction "2_2") (pintype "passive"))
      (node (ref "C10") (pin "1") (pinfunction "1_1") (pintype "passive"))
      (node (ref "C11") (pin "2") (pinfunction "2_2") (pintype "passive"))
      (node (ref "C12") (pin "2") (pinfunction "2_2") (pintype "passive"))
      (node (ref "C13") (pin "2") (pinfunction "2_2") (pintype "passive"))
      (node (ref "C2") (pin "2") (pinfunction "2_2") (pintype "passive"))
      (node (ref "C3") (pin "2") (pinfunction "2_2") (pintype "passive"))
      (node (ref "C4") (pin "2") (pinfunction "2_2") (pintype "passive"))
      (node (ref "C5") (pin "2") (pinfunction "2_2") (pintype "passive"))
      (node (ref "C6") (pin "1") (pinfunction "1_1") (pintype "passive"))
      (node (ref "C7") (pin "2") (pinfunction "2_2") (pintype "passive"))
      (node (ref "C8") (pin "2") (pinfunction "2_2") (pintype "passive"))
      (node (ref "C9") (pin "2") (pinfunction "2_2") (pintype "passive"))
      (node (ref "IC1") (pin "1") (pinfunction "ADJ_1") (pintype "input"))
      (node (ref "IC2") (pin "14") (pinfunction "GND_14") (pintype "power_in"))
      (node (ref "IC2") (pin "20") (pinfunction "~{CE}_20") (pintype "input"))
      (node (ref "IC3") (pin "10") (pinfunction "GNDIO_10") (pintype "power_in"))
      (node (ref "IC3") (pin "11") (pinfunction "GNDINT_11") (pintype "power_in"))
      (node (ref "IC3") (pin "32") (pinfunction "GNDIO_32") (pintype "power_in"))
      (node (ref "IC3") (pin "46") (pinfunction "GNDIO_46") (pintype "power_in"))
      (node (ref "IC3") (pin "60") (pinfunction "GNDIO_60") (pintype "power_in"))
      (node (ref "IC3") (pin "65") (pinfunction "GNDINT_65") (pintype "power_in"))
      (node (ref "IC3") (pin "79") (pinfunction "GNDIO_79") (pintype "power_in"))
      (node (ref "IC3") (pin "93") (pinfunction "GNDIO_93") (pintype "power_in"))
      (node (ref "IC4") (pin "P$16") (pinfunction "GND_P$16") (pintype "input"))
      (node (ref "IC4") (pin "P$22") (pinfunction "/CE1_P$22") (pintype "input"))
      (node (ref "JTAG") (pin "10") (pinfunction "KL_10") (pintype "passive"))
      (node (ref "JTAG") (pin "2") (pinfunction "KL_2") (pintype "passive"))
      (node (ref "JUMPER_E") (pin "3") (pinfunction "3_3") (pintype "bidirectional"))
      (node (ref "JUMPER_E") (pin "4") (pinfunction "4_4") (pintype "bidirectional"))
      (node (ref "NMI") (pin "1") (pinfunction "GND1_1") (pintype "passive"))
      (node (ref "NMI") (pin "3") (pinfunction "3_3") (pintype "passive"))
      (node (ref "NMI") (pin "4") (pinfunction "GND_4") (pintype "passive"))
      (node (ref "Q1") (pin "2") (pinfunction "GND_2") (pintype "power_in"))
      (node (ref "R4") (pin "2") (pinfunction "2_2") (pintype "passive"))
      (node (ref "RESET") (pin "1") (pinfunction "GND1_1") (pintype "passive"))
      (node (ref "RESET") (pin "3") (pinfunction "3_3") (pintype "passive"))
      (node (ref "RESET") (pin "4") (pinfunction "GND_4") (pintype "passive"))
      (node (ref "SDCARD") (pin "3") (pinfunction "VSS1_3") (pintype "power_in"))
      (node (ref "SDCARD") (pin "6") (pinfunction "VSS2_6") (pintype "power_in"))
      (node (ref "SDCARD") (pin "M1") (pinfunction "GND_M1") (pintype "power_in"))
      (node (ref "SDCARD") (pin "M2") (pinfunction "GND_M2") (pintype "power_in"))
      (node (ref "SDCARD") (pin "M3") (pinfunction "GND_M3") (pintype "power_in"))
      (node (ref "SDCARD") (pin "M4") (pinfunction "GND_M4") (pintype "power_in"))
      (node (ref "U$1") (pin "A14") (pinfunction "GND_A14") (pintype "bidirectional"))
      (node (ref "U$1") (pin "A6") (pinfunction "GND1_A6") (pintype "bidirectional"))
      (node (ref "U$1") (pin "A7") (pinfunction "GND2_A7") (pintype "bidirectional"))
      (node (ref "ZX_EXPANSION_BUS_CONNECTOR") (pin "11") (pinfunction "11_11") (pintype "passive"))
      (node (ref "ZX_EXPANSION_BUS_CONNECTOR") (pin "13") (pinfunction "13_13") (pintype "passive"))
      (node (ref "ZX_EXPANSION_BUS_CONNECTOR") (pin "27") (pinfunction "27_27") (pintype "passive"))
    )
    (net (code "82") (name "Net-(E-PadA)") (class "Default")
      (node (ref "E") (pin "A") (pinfunction "A_A") (pintype "passive"))
      (node (ref "R1") (pin "2") (pinfunction "2_2") (pintype "passive"))
    )
    (net (code "83") (name "Net-(R5-Pad1)") (class "Default")
      (node (ref "R5") (pin "1") (pinfunction "1_1") (pintype "passive"))
      (node (ref "SD") (pin "A") (pinfunction "A_A") (pintype "passive"))
    )
    (net (code "84") (name "Net-(SDCARD-DAT1)") (class "Default")
      (node (ref "R7") (pin "1") (pinfunction "1_1") (pintype "passive"))
      (node (ref "SDCARD") (pin "8") (pinfunction "DAT1_8") (pintype "bidirectional"))
    )
    (net (code "85") (name "Net-(SDCARD-DAT2)") (class "Default")
      (node (ref "R8") (pin "1") (pinfunction "1_1") (pintype "passive"))
      (node (ref "SDCARD") (pin "9") (pinfunction "DAT2_9") (pintype "bidirectional"))
    )
    (net (code "86") (name "unconnected-(IC2-RDY{slash}~{BSY}-Pad1)") (class "Default")
      (node (ref "IC2") (pin "1") (pinfunction "RDY/~{BSY}_1") (pintype "output"))
    )
    (net (code "87") (name "unconnected-(IC3-B1{slash}5-Pad7)") (class "Default")
      (node (ref "IC3") (pin "7") (pinfunction "B1/5_7") (pintype "bidirectional"))
    )
    (net (code "88") (name "unconnected-(IC3-B1{slash}13-Pad15)") (class "Default")
      (node (ref "IC3") (pin "15") (pinfunction "B1/13_15") (pintype "bidirectional"))
    )
    (net (code "89") (name "unconnected-(IC3-B1{slash}14-Pad16)") (class "Default")
      (node (ref "IC3") (pin "16") (pinfunction "B1/14_16") (pintype "bidirectional"))
    )
    (net (code "90") (name "unconnected-(IC3-B1{slash}15-Pad17)") (class "Default")
      (node (ref "IC3") (pin "17") (pinfunction "B1/15_17") (pintype "bidirectional"))
    )
    (net (code "91") (name "unconnected-(IC3-B1{slash}16-Pad18)") (class "Default")
      (node (ref "IC3") (pin "18") (pinfunction "B1/16_18") (pintype "bidirectional"))
    )
    (net (code "92") (name "unconnected-(IC3-B1{slash}17-Pad19)") (class "Default")
      (node (ref "IC3") (pin "19") (pinfunction "B1/17_19") (pintype "bidirectional"))
    )
    (net (code "93") (name "unconnected-(IC3-B1{slash}18-Pad20)") (class "Default")
      (node (ref "IC3") (pin "20") (pinfunction "B1/18_20") (pintype "bidirectional"))
    )
    (net (code "94") (name "unconnected-(IC3-B1{slash}19-Pad21)") (class "Default")
      (node (ref "IC3") (pin "21") (pinfunction "B1/19_21") (pintype "bidirectional"))
    )
    (net (code "95") (name "unconnected-(IC3-B1{slash}29-Pad30)") (class "Default")
      (node (ref "IC3") (pin "30") (pinfunction "B1/29_30") (pintype "bidirectional"))
    )
    (net (code "96") (name "unconnected-(IC3-B1{slash}32-Pad33)") (class "Default")
      (node (ref "IC3") (pin "33") (pinfunction "B1/32_33") (pintype "bidirectional"))
    )
    (net (code "97") (name "unconnected-(IC3-B1{slash}34-Pad35)") (class "Default")
      (node (ref "IC3") (pin "35") (pinfunction "B1/34_35") (pintype "bidirectional"))
    )
    (net (code "98") (name "unconnected-(IC3-B1{slash}35-Pad36)") (class "Default")
      (node (ref "IC3") (pin "36") (pinfunction "B1/35_36") (pintype "bidirectional"))
    )
    (net (code "99") (name "unconnected-(IC3-B1{slash}36-Pad37)") (class "Default")
      (node (ref "IC3") (pin "37") (pinfunction "B1/36_37") (pintype "bidirectional"))
    )
    (net (code "100") (name "unconnected-(IC3-B1{slash}37-Pad38)") (class "Default")
      (node (ref "IC3") (pin "38") (pinfunction "B1/37_38") (pintype "bidirectional"))
    )
    (net (code "101") (name "unconnected-(IC3-B1{slash}38-Pad39)") (class "Default")
      (node (ref "IC3") (pin "39") (pinfunction "B1/38_39") (pintype "bidirectional"))
    )
    (net (code "102") (name "unconnected-(IC3-B1{slash}39-Pad40)") (class "Default")
      (node (ref "IC3") (pin "40") (pinfunction "B1/39_40") (pintype "bidirectional"))
    )
    (net (code "103") (name "unconnected-(IC3-B1{slash}40-Pad41)") (class "Default")
      (node (ref "IC3") (pin "41") (pinfunction "B1/40_41") (pintype "bidirectional"))
    )
    (net (code "104") (name "unconnected-(IC3-B1{slash}41-Pad42)") (class "Default")
      (node (ref "IC3") (pin "42") (pinfunction "B1/41_42") (pintype "bidirectional"))
    )
    (net (code "105") (name "unconnected-(IC3-B1{slash}42-DEV_OE-Pad43)") (class "Default")
      (node (ref "IC3") (pin "43") (pinfunction "B1/42-DEV_OE_43") (pintype "bidirectional"))
    )
    (net (code "106") (name "unconnected-(IC3-B1{slash}47-Pad48)") (class "Default")
      (node (ref "IC3") (pin "48") (pinfunction "B1/47_48") (pintype "bidirectional"))
    )
    (net (code "107") (name "unconnected-(IC3-B1{slash}48-Pad49)") (class "Default")
      (node (ref "IC3") (pin "49") (pinfunction "B1/48_49") (pintype "bidirectional"))
    )
    (net (code "108") (name "unconnected-(IC3-B1{slash}49-Pad50)") (class "Default")
      (node (ref "IC3") (pin "50") (pinfunction "B1/49_50") (pintype "bidirectional"))
    )
    (net (code "109") (name "unconnected-(IC3-B2{slash}54-Pad55)") (class "Default")
      (node (ref "IC3") (pin "55") (pinfunction "B2/54_55") (pintype "bidirectional"))
    )
    (net (code "110") (name "unconnected-(IC3-B2{slash}55-Pad56)") (class "Default")
      (node (ref "IC3") (pin "56") (pinfunction "B2/55_56") (pintype "bidirectional"))
    )
    (net (code "111") (name "unconnected-(JTAGG-KL-Pad6)") (class "Default")
      (node (ref "JTAG") (pin "6") (pinfunction "KL_6") (pintype "passive"))
    )
    (net (code "112") (name "unconnected-(JTAGH-KL-Pad7)") (class "Default")
      (node (ref "JTAG") (pin "7") (pinfunction "KL_7") (pintype "passive"))
    )
    (net (code "113") (name "unconnected-(JTAGI-KL-Pad8)") (class "Default")
      (node (ref "JTAG") (pin "8") (pinfunction "KL_8") (pintype "passive"))
    )
    (net (code "114") (name "unconnected-(SDCARD-CDI#-Pad10)") (class "Default")
      (node (ref "SDCARD") (pin "10") (pinfunction "CDI#_10") (pintype "output"))
    )
    (net (code "115") (name "unconnected-(SDCARD-WP-Pad11)") (class "Default")
      (node (ref "SDCARD") (pin "11") (pinfunction "WP_11") (pintype "output"))
    )
  )
)
